# 03_-LED7SEG.net
KiCad netlist of a schematic drawn in Altium Designer
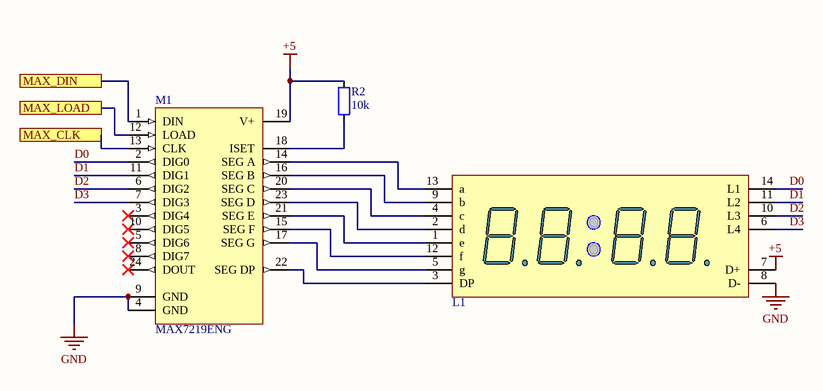
[diagram p0: [03]-LED7SEG.SchDoc]

(export (version "E")
  (design (tool "Eeschema 10.0.6"))
  (components
    (comp (ref "L1")
      (value "Led 7 Seg 4 digit - Anode")
      (footprint "7SEGQ")
      (libsource (lib "My Library") (part "LED7SEG-4DIGIT-A"))
    )
    (comp (ref "M1")
      (value "MAX7219ENG")
      (footprint "SO24_L")
      (description "Serially Interfaced, 8-Digit LED Display Driver")
      (fields (field (name "PUBLISHER") "Altium Limited"))
      (libsource (lib "My Library") (part "MAX7219ENG"))
    )
    (comp (ref "R2")
      (value "10k")
      (footprint "RES_SMD_0805")
      (description "Resistor - DIP")
      (libsource (lib "My Library") (part "Resistor - DIP"))
    )
  )
  (nets
    (net (code "1") (name "+5") (class "Default")
      (node (ref "L1") (pin "7") (pinfunction "D+_7") (pintype "passive"))
      (node (ref "M1") (pin "19") (pinfunction "V+_19") (pintype "power_in"))
      (node (ref "R2") (pin "2") (pinfunction "2_2") (pintype "passive"))
    )
    (net (code "2") (name "/D0") (class "Default")
      (node (ref "L1") (pin "14") (pinfunction "L1_14") (pintype "passive"))
      (node (ref "M1") (pin "2") (pinfunction "DIG0_2") (pintype "output"))
    )
    (net (code "3") (name "/D1") (class "Default")
      (node (ref "L1") (pin "11") (pinfunction "L2_11") (pintype "passive"))
      (node (ref "M1") (pin "11") (pinfunction "DIG1_11") (pintype "output"))
    )
    (net (code "4") (name "/D2") (class "Default")
      (node (ref "L1") (pin "10") (pinfunction "L3_10") (pintype "passive"))
      (node (ref "M1") (pin "6") (pinfunction "DIG2_6") (pintype "output"))
    )
    (net (code "5") (name "/D3") (class "Default")
      (node (ref "L1") (pin "6") (pinfunction "L4_6") (pintype "passive"))
      (node (ref "M1") (pin "7") (pinfunction "DIG3_7") (pintype "output"))
    )
    (net (code "6") (name "/MAX_CLK") (class "Default")
      (node (ref "M1") (pin "13") (pinfunction "CLK_13") (pintype "input"))
    )
    (net (code "7") (name "/MAX_DIN") (class "Default")
      (node (ref "M1") (pin "1") (pinfunction "DIN_1") (pintype "input"))
    )
    (net (code "8") (name "/MAX_LOAD") (class "Default")
      (node (ref "M1") (pin "12") (pinfunction "LOAD_12") (pintype "input"))
    )
    (net (code "9") (name "GND") (class "Default")
      (node (ref "L1") (pin "8") (pinfunction "D-_8") (pintype "passive"))
      (node (ref "M1") (pin "4") (pinfunction "GND_4") (pintype "power_in"))
      (node (ref "M1") (pin "9") (pinfunction "GND_9") (pintype "power_in"))
    )
    (net (code "10") (name "Net-(L1-DP)") (class "Default")
      (node (ref "L1") (pin "3") (pinfunction "DP_3") (pintype "passive"))
      (node (ref "M1") (pin "22") (pinfunction "SEG_DP_22") (pintype "output"))
    )
    (net (code "11") (name "Net-(L1-a)") (class "Default")
      (node (ref "L1") (pin "13") (pinfunction "a_13") (pintype "passive"))
      (node (ref "M1") (pin "14") (pinfunction "SEG_A_14") (pintype "output"))
    )
    (net (code "12") (name "Net-(L1-b)") (class "Default")
      (node (ref "L1") (pin "9") (pinfunction "b_9") (pintype "passive"))
      (node (ref "M1") (pin "16") (pinfunction "SEG_B_16") (pintype "output"))
    )
    (net (code "13") (name "Net-(L1-c)") (class "Default")
      (node (ref "L1") (pin "4") (pinfunction "c_4") (pintype "passive"))
      (node (ref "M1") (pin "20") (pinfunction "SEG_C_20") (pintype "output"))
    )
    (net (code "14") (name "Net-(L1-d)") (class "Default")
      (node (ref "L1") (pin "2") (pinfunction "d_2") (pintype "passive"))
      (node (ref "M1") (pin "23") (pinfunction "SEG_D_23") (pintype "output"))
    )
    (net (code "15") (name "Net-(L1-e)") (class "Default")
      (node (ref "L1") (pin "1") (pinfunction "e_1") (pintype "passive"))
      (node (ref "M1") (pin "21") (pinfunction "SEG_E_21") (pintype "output"))
    )
    (net (code "16") (name "Net-(L1-f)") (class "Default")
      (node (ref "L1") (pin "12") (pinfunction "f_12") (pintype "passive"))
      (node (ref "M1") (pin "15") (pinfunction "SEG_F_15") (pintype "output"))
    )
    (net (code "17") (name "Net-(L1-g)") (class "Default")
      (node (ref "L1") (pin "5") (pinfunction "g_5") (pintype "passive"))
      (node (ref "M1") (pin "17") (pinfunction "SEG_G_17") (pintype "output"))
    )
    (net (code "18") (name "Net-(M1-ISET)") (class "Default")
      (node (ref "M1") (pin "18") (pinfunction "ISET_18") (pintype "passive"))
      (node (ref "R2") (pin "1") (pinfunction "1_1") (pintype "passive"))
    )
    (net (code "19") (name "unconnected-(M1-DIG4-Pad3)") (class "Default")
      (node (ref "M1") (pin "3") (pinfunction "DIG4_3") (pintype "output+no_connect"))
    )
    (net (code "20") (name "unconnected-(M1-DIG5-Pad10)") (class "Default")
      (node (ref "M1") (pin "10") (pinfunction "DIG5_10") (pintype "output+no_connect"))
    )
    (net (code "21") (name "unconnected-(M1-DIG6-Pad5)") (class "Default")
      (node (ref "M1") (pin "5") (pinfunction "DIG6_5") (pintype "output+no_connect"))
    )
    (net (code "22") (name "unconnected-(M1-DIG7-Pad8)") (class "Default")
      (node (ref "M1") (pin "8") (pinfunction "DIG7_8") (pintype "output+no_connect"))
    )
    (net (code "23") (name "unconnected-(M1-DOUT-Pad24)") (class "Default")
      (node (ref "M1") (pin "24") (pinfunction "DOUT_24") (pintype "output+no_connect"))
    )
  )
)
